# temp_sensor.net
KiCad netlist of a schematic drawn in Altium Designer
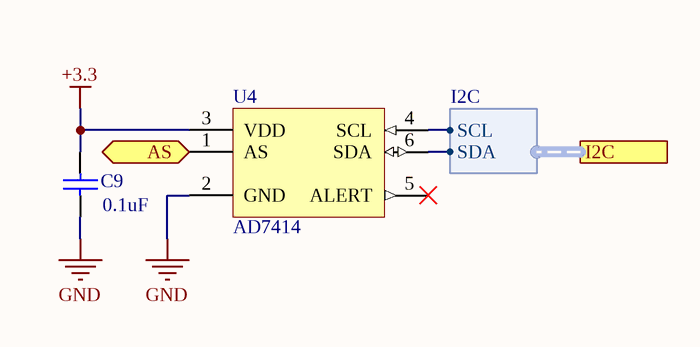
[diagram p0: temp_sensor.SchDoc]

(export (version "E")
  (design (tool "Eeschema 10.0.6"))
  (components
    (comp (ref "C9")
      (value "0.1uF")
      (footprint "C0603")
      (description "Capacitor")
      (fields (field (name "Comment") "Cap") (field (name "PUBLISHER") "Altium Limited"))
      (libsource (lib "Miscellaneous Devices") (part "Cap"))
    )
    (comp (ref "U4")
      (value "AD7414")
      (footprint "AD7414")
      (description "ANALOG DEVICES - AD7414ARTZ-0500RL7. - TEMP SENSOR, 10BIT, SMB/12C, SOT23-6")
      (libsource (lib "AD7414") (part "AD7414"))
    )
  )
  (nets
    (net (code "2") (name "+3.3") (class "Default")
      (node (ref "C9") (pin "2") (pinfunction "2_2") (pintype "passive"))
      (node (ref "U4") (pin "3") (pinfunction "VDD_3") (pintype "power_in"))
    )
    (net (code "3") (name "/AS") (class "Default")
      (node (ref "U4") (pin "1") (pinfunction "AS_1") (pintype "passive"))
    )
    (net (code "4") (name "/SCL") (class "Default")
      (node (ref "U4") (pin "4") (pinfunction "SCL_4") (pintype "input"))
    )
    (net (code "5") (name "/SDA") (class "Default")
      (node (ref "U4") (pin "6") (pinfunction "SDA_6") (pintype "bidirectional"))
    )
    (net (code "7") (name "GND") (class "Default")
      (node (ref "C9") (pin "1") (pinfunction "1_1") (pintype "passive"))
      (node (ref "U4") (pin "2") (pinfunction "GND_2") (pintype "power_in"))
    )
    (net (code "8") (name "unconnected-(U4-ALERT-Pad5)") (class "Default")
      (node (ref "U4") (pin "5") (pinfunction "ALERT_5") (pintype "output+no_connect"))
    )
  )
)
